# ATM90E36_Breakout.net
KiCad netlist of a schematic drawn in EAGLE
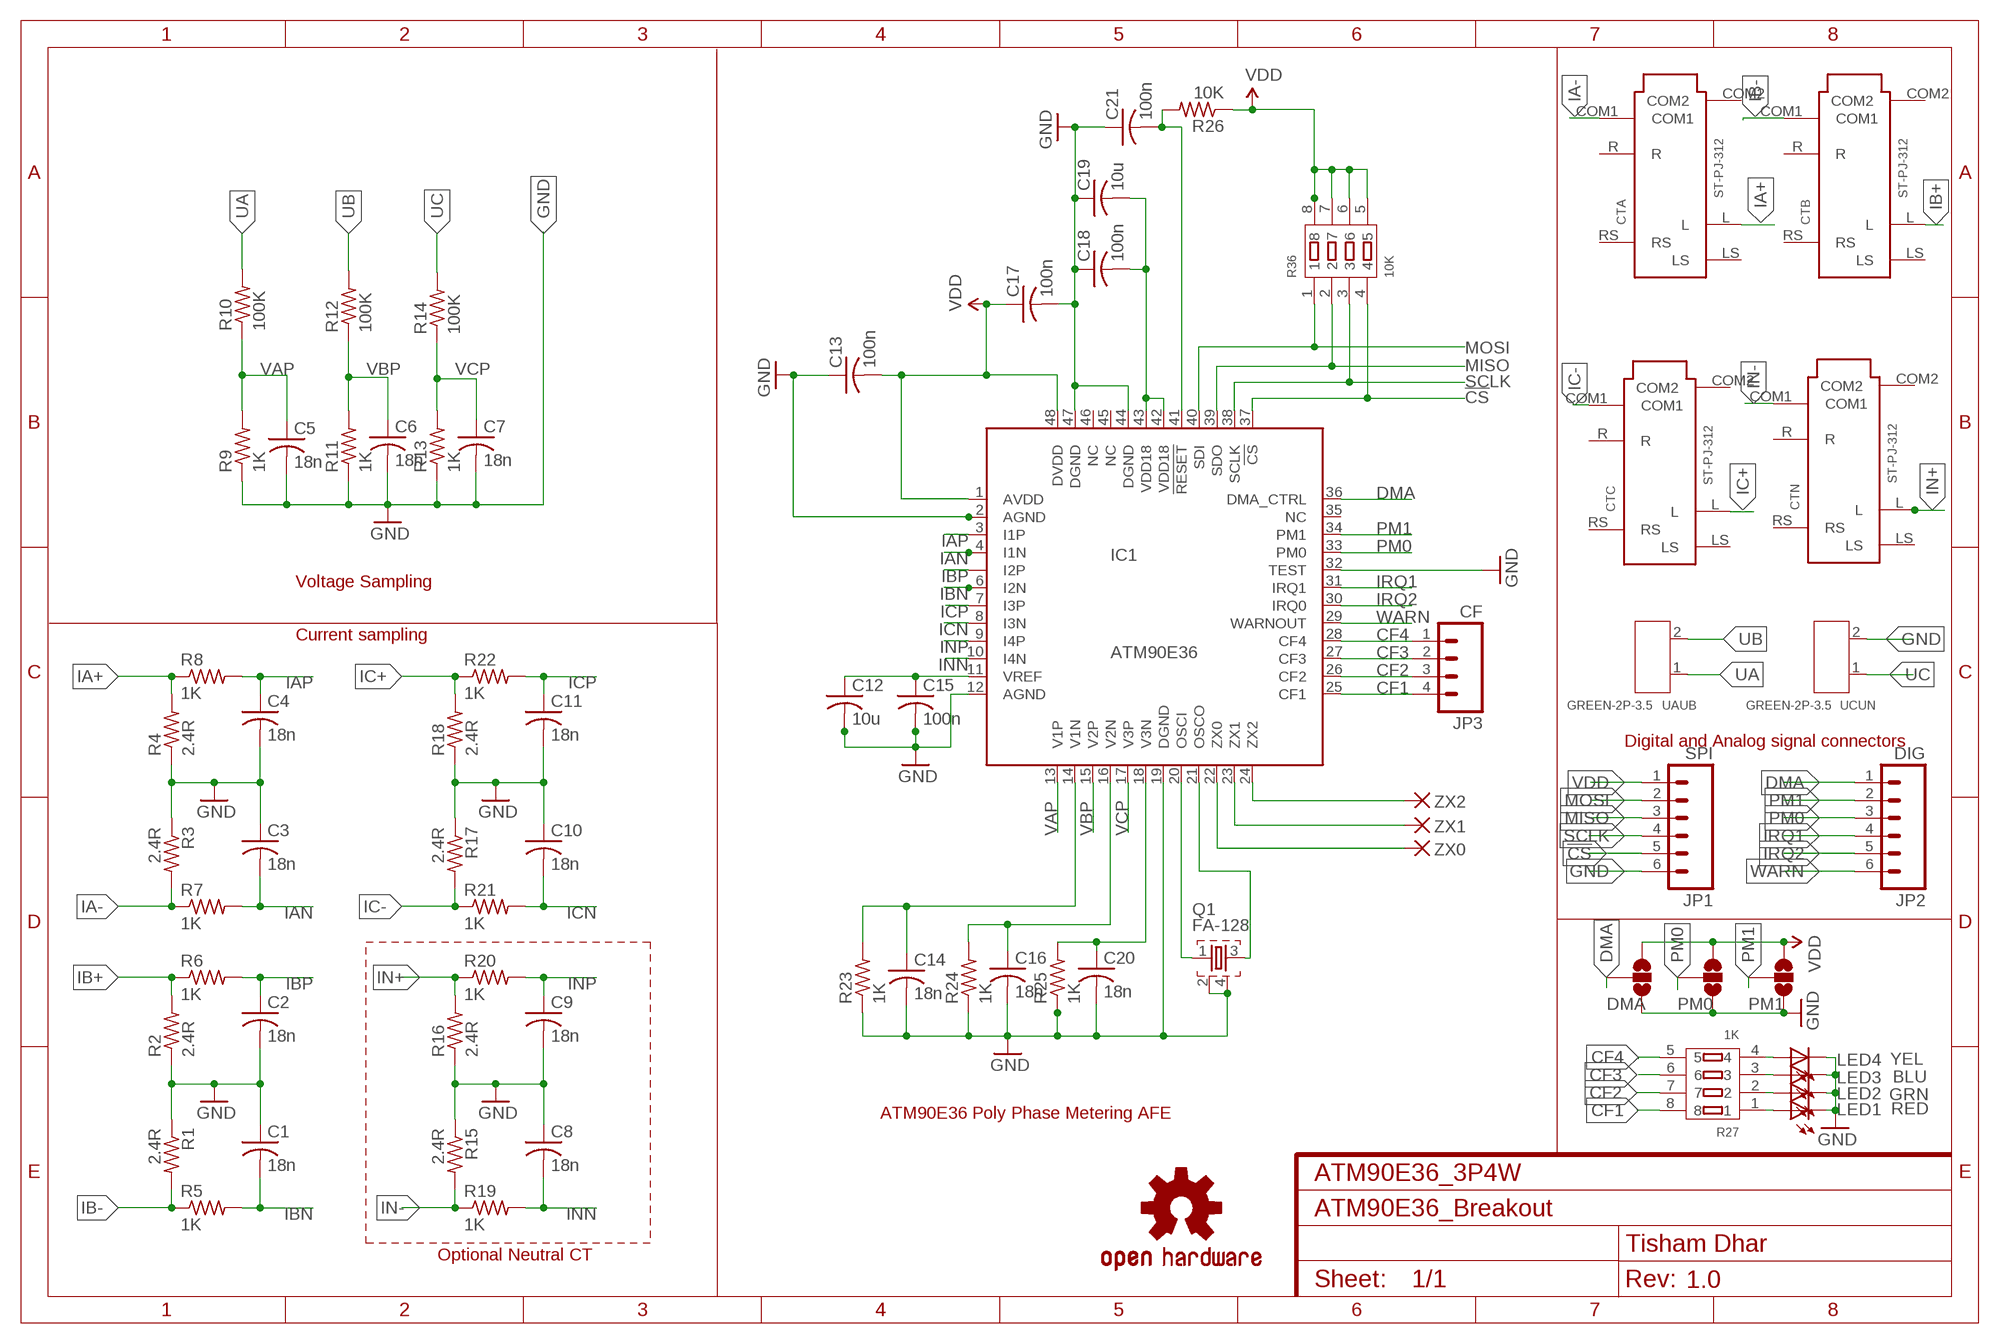
[diagram p0: schematic, sheet 1]

(export (version "E")
  (design (tool "Eeschema 10.0.6"))
  (components
    (comp (ref "C1")
      (value "18n")
      (footprint "eagle-import:C0603")
      (libsource (lib "eagle-import") (part "C-USC0603"))
    )
    (comp (ref "C2")
      (value "18n")
      (footprint "eagle-import:C0603")
      (libsource (lib "eagle-import") (part "C-USC0603"))
    )
    (comp (ref "C3")
      (value "18n")
      (footprint "eagle-import:C0603")
      (libsource (lib "eagle-import") (part "C-USC0603"))
    )
    (comp (ref "C4")
      (value "18n")
      (footprint "eagle-import:C0603")
      (libsource (lib "eagle-import") (part "C-USC0603"))
    )
    (comp (ref "C5")
      (value "18n")
      (footprint "eagle-import:C0603")
      (libsource (lib "eagle-import") (part "C-USC0603"))
    )
    (comp (ref "C6")
      (value "18n")
      (footprint "eagle-import:C0603")
      (libsource (lib "eagle-import") (part "C-USC0603"))
    )
    (comp (ref "C7")
      (value "18n")
      (footprint "eagle-import:C0603")
      (libsource (lib "eagle-import") (part "C-USC0603"))
    )
    (comp (ref "C8")
      (value "18n")
      (footprint "eagle-import:C0603")
      (libsource (lib "eagle-import") (part "C-USC0603"))
    )
    (comp (ref "C9")
      (value "18n")
      (footprint "eagle-import:C0603")
      (libsource (lib "eagle-import") (part "C-USC0603"))
    )
    (comp (ref "C10")
      (value "18n")
      (footprint "eagle-import:C0603")
      (libsource (lib "eagle-import") (part "C-USC0603"))
    )
    (comp (ref "C11")
      (value "18n")
      (footprint "eagle-import:C0603")
      (libsource (lib "eagle-import") (part "C-USC0603"))
    )
    (comp (ref "C12")
      (value "10u")
      (footprint "eagle-import:C0805")
      (libsource (lib "eagle-import") (part "C-USC0805"))
    )
    (comp (ref "C13")
      (value "100n")
      (footprint "eagle-import:C0603")
      (libsource (lib "eagle-import") (part "C-USC0603"))
    )
    (comp (ref "C14")
      (value "18n")
      (footprint "eagle-import:C0603")
      (libsource (lib "eagle-import") (part "C-USC0603"))
    )
    (comp (ref "C15")
      (value "100n")
      (footprint "eagle-import:C0603")
      (libsource (lib "eagle-import") (part "C-USC0603"))
    )
    (comp (ref "C16")
      (value "18n")
      (footprint "eagle-import:C0603")
      (libsource (lib "eagle-import") (part "C-USC0603"))
    )
    (comp (ref "C17")
      (value "100n")
      (footprint "eagle-import:C0603")
      (libsource (lib "eagle-import") (part "C-USC0603"))
    )
    (comp (ref "C18")
      (value "100n")
      (footprint "eagle-import:C0603")
      (libsource (lib "eagle-import") (part "C-USC0603"))
    )
    (comp (ref "C19")
      (value "10u")
      (footprint "eagle-import:C0805")
      (libsource (lib "eagle-import") (part "C-USC0805"))
    )
    (comp (ref "C20")
      (value "18n")
      (footprint "eagle-import:C0603")
      (libsource (lib "eagle-import") (part "C-USC0603"))
    )
    (comp (ref "C21")
      (value "100n")
      (footprint "eagle-import:C0603")
      (libsource (lib "eagle-import") (part "C-USC0603"))
    )
    (comp (ref "CTA")
      (value "ST-PJ-312")
      (footprint "eagle-import:AUDIO6P-SMD-3.5-14.0X6.4X5.0MM")
      (libsource (lib "eagle-import") (part "AUDIO-JACK-6P-SMD(ST-PJ-312)"))
    )
    (comp (ref "CTB")
      (value "ST-PJ-312")
      (footprint "eagle-import:AUDIO6P-SMD-3.5-14.0X6.4X5.0MM")
      (libsource (lib "eagle-import") (part "AUDIO-JACK-6P-SMD(ST-PJ-312)"))
    )
    (comp (ref "CTC")
      (value "ST-PJ-312")
      (footprint "eagle-import:AUDIO6P-SMD-3.5-14.0X6.4X5.0MM")
      (libsource (lib "eagle-import") (part "AUDIO-JACK-6P-SMD(ST-PJ-312)"))
    )
    (comp (ref "CTN")
      (value "ST-PJ-312")
      (footprint "eagle-import:AUDIO6P-SMD-3.5-14.0X6.4X5.0MM")
      (libsource (lib "eagle-import") (part "AUDIO-JACK-6P-SMD(ST-PJ-312)"))
    )
    (comp (ref "DMA")
      (value "JUMPER-PAD-3-NOFULL_BOX_SILK")
      (footprint "eagle-import:PAD-JUMPER-3-NO_YES_SILK_FULL_BOX")
      (libsource (lib "eagle-import") (part "JUMPER-PAD-3-NOFULL_BOX_SILK"))
    )
    (comp (ref "IC1")
      (value "ATM90E36")
      (footprint "eagle-import:TQFP48")
      (libsource (lib "eagle-import") (part "ATM90E36"))
    )
    (comp (ref "JP1")
      (value "SPI")
      (footprint "eagle-import:1X06_LOCK")
      (libsource (lib "eagle-import") (part "M06LOCK"))
    )
    (comp (ref "JP2")
      (value "DIG")
      (footprint "eagle-import:1X06_LOCK")
      (libsource (lib "eagle-import") (part "M06LOCK"))
    )
    (comp (ref "JP3")
      (value "CF")
      (footprint "eagle-import:1X04_LOCK")
      (libsource (lib "eagle-import") (part "M04LOCK"))
    )
    (comp (ref "LED1")
      (value "RED")
      (footprint "eagle-import:CHIP-LED0603")
      (libsource (lib "eagle-import") (part "LEDCHIP-LED0603"))
    )
    (comp (ref "LED2")
      (value "GRN")
      (footprint "eagle-import:CHIP-LED0603")
      (libsource (lib "eagle-import") (part "LEDCHIP-LED0603"))
    )
    (comp (ref "LED3")
      (value "BLU")
      (footprint "eagle-import:CHIP-LED0603")
      (libsource (lib "eagle-import") (part "LEDCHIP-LED0603"))
    )
    (comp (ref "LED4")
      (value "YEL")
      (footprint "eagle-import:CHIP-LED0603")
      (libsource (lib "eagle-import") (part "LEDCHIP-LED0603"))
    )
    (comp (ref "LOGO1")
      (value "OSHW-LOGOM")
      (footprint "eagle-import:OSHW-LOGO-M")
      (libsource (lib "eagle-import") (part "OSHW-LOGOM"))
    )
    (comp (ref "PM0")
      (value "JUMPER-PAD-3-NOFULL_BOX_SILK")
      (footprint "eagle-import:PAD-JUMPER-3-NO_YES_SILK_FULL_BOX")
      (libsource (lib "eagle-import") (part "JUMPER-PAD-3-NOFULL_BOX_SILK"))
    )
    (comp (ref "PM1")
      (value "JUMPER-PAD-3-NOFULL_BOX_SILK")
      (footprint "eagle-import:PAD-JUMPER-3-NO_YES_SILK_FULL_BOX")
      (libsource (lib "eagle-import") (part "JUMPER-PAD-3-NOFULL_BOX_SILK"))
    )
    (comp (ref "Q1")
      (value "FA-128")
      (footprint "eagle-import:FA-128")
      (libsource (lib "eagle-import") (part "FA-128"))
    )
    (comp (ref "R1")
      (value "2.4R")
      (footprint "eagle-import:R0603")
      (libsource (lib "eagle-import") (part "R-US_R0603"))
    )
    (comp (ref "R2")
      (value "2.4R")
      (footprint "eagle-import:R0603")
      (libsource (lib "eagle-import") (part "R-US_R0603"))
    )
    (comp (ref "R3")
      (value "2.4R")
      (footprint "eagle-import:R0603")
      (libsource (lib "eagle-import") (part "R-US_R0603"))
    )
    (comp (ref "R4")
      (value "2.4R")
      (footprint "eagle-import:R0603")
      (libsource (lib "eagle-import") (part "R-US_R0603"))
    )
    (comp (ref "R5")
      (value "1K")
      (footprint "eagle-import:R0603")
      (libsource (lib "eagle-import") (part "R-US_R0603"))
    )
    (comp (ref "R6")
      (value "1K")
      (footprint "eagle-import:R0603")
      (libsource (lib "eagle-import") (part "R-US_R0603"))
    )
    (comp (ref "R7")
      (value "1K")
      (footprint "eagle-import:R0603")
      (libsource (lib "eagle-import") (part "R-US_R0603"))
    )
    (comp (ref "R8")
      (value "1K")
      (footprint "eagle-import:R0603")
      (libsource (lib "eagle-import") (part "R-US_R0603"))
    )
    (comp (ref "R9")
      (value "1K")
      (footprint "eagle-import:R0603")
      (libsource (lib "eagle-import") (part "R-US_R0603"))
    )
    (comp (ref "R10")
      (value "100K")
      (footprint "eagle-import:R0603")
      (libsource (lib "eagle-import") (part "R-US_R0603"))
    )
    (comp (ref "R11")
      (value "1K")
      (footprint "eagle-import:R0603")
      (libsource (lib "eagle-import") (part "R-US_R0603"))
    )
    (comp (ref "R12")
      (value "100K")
      (footprint "eagle-import:R0603")
      (libsource (lib "eagle-import") (part "R-US_R0603"))
    )
    (comp (ref "R13")
      (value "1K")
      (footprint "eagle-import:R0603")
      (libsource (lib "eagle-import") (part "R-US_R0603"))
    )
    (comp (ref "R14")
      (value "100K")
      (footprint "eagle-import:R0603")
      (libsource (lib "eagle-import") (part "R-US_R0603"))
    )
    (comp (ref "R15")
      (value "2.4R")
      (footprint "eagle-import:R0603")
      (libsource (lib "eagle-import") (part "R-US_R0603"))
    )
    (comp (ref "R16")
      (value "2.4R")
      (footprint "eagle-import:R0603")
      (libsource (lib "eagle-import") (part "R-US_R0603"))
    )
    (comp (ref "R17")
      (value "2.4R")
      (footprint "eagle-import:R0603")
      (libsource (lib "eagle-import") (part "R-US_R0603"))
    )
    (comp (ref "R18")
      (value "2.4R")
      (footprint "eagle-import:R0603")
      (libsource (lib "eagle-import") (part "R-US_R0603"))
    )
    (comp (ref "R19")
      (value "1K")
      (footprint "eagle-import:R0603")
      (libsource (lib "eagle-import") (part "R-US_R0603"))
    )
    (comp (ref "R20")
      (value "1K")
      (footprint "eagle-import:R0603")
      (libsource (lib "eagle-import") (part "R-US_R0603"))
    )
    (comp (ref "R21")
      (value "1K")
      (footprint "eagle-import:R0603")
      (libsource (lib "eagle-import") (part "R-US_R0603"))
    )
    (comp (ref "R22")
      (value "1K")
      (footprint "eagle-import:R0603")
      (libsource (lib "eagle-import") (part "R-US_R0603"))
    )
    (comp (ref "R23")
      (value "1K")
      (footprint "eagle-import:R0603")
      (libsource (lib "eagle-import") (part "R-US_R0603"))
    )
    (comp (ref "R24")
      (value "1K")
      (footprint "eagle-import:R0603")
      (libsource (lib "eagle-import") (part "R-US_R0603"))
    )
    (comp (ref "R25")
      (value "1K")
      (footprint "eagle-import:R0603")
      (libsource (lib "eagle-import") (part "R-US_R0603"))
    )
    (comp (ref "R26")
      (value "10K")
      (footprint "eagle-import:R0603")
      (libsource (lib "eagle-import") (part "R-US_R0603"))
    )
    (comp (ref "R27")
      (value "1K")
      (footprint "eagle-import:RA1206-8")
      (fields (field (name "MPN") "Chip-Array-Series-1%"))
      (libsource (lib "eagle-import") (part "SMD-RES-ARRAY-1K-4R(RA1206-8)"))
    )
    (comp (ref "R36")
      (value "10K")
      (footprint "eagle-import:RA1206-8")
      (fields (field (name "MPN") "Chip-Array-Series-1%"))
      (libsource (lib "eagle-import") (part "SMD-RES-ARRAY-1K-4R(RA1206-8)"))
    )
    (comp (ref "UAUB")
      (value "GREEN-2P-3.5")
      (footprint "eagle-import:H2-3.5-7.0X7.0MM")
      (libsource (lib "eagle-import") (part "SCREW-TERMINAL-GREEN(2P-3.5)"))
    )
    (comp (ref "UCUN")
      (value "GREEN-2P-3.5")
      (footprint "eagle-import:H2-3.5-7.0X7.0MM")
      (libsource (lib "eagle-import") (part "SCREW-TERMINAL-GREEN(2P-3.5)"))
    )
    (comp (ref "ZX0")
      (value "ZX0")
      (footprint "eagle-import:SMD1,27-2,54")
      (libsource (lib "eagle-import") (part "SMD2"))
    )
    (comp (ref "ZX1")
      (value "ZX1")
      (footprint "eagle-import:SMD1,27-2,54")
      (libsource (lib "eagle-import") (part "SMD2"))
    )
    (comp (ref "ZX2")
      (value "ZX0")
      (footprint "eagle-import:SMD1,27-2,54")
      (libsource (lib "eagle-import") (part "SMD2"))
    )
  )
  (nets
    (net (code "1") (name "/IAN") (class "Default")
      (node (ref "C3") (pin "2") (pinfunction "2_2") (pintype "passive"))
      (node (ref "IC1") (pin "4") (pinfunction "I1N_4") (pintype "input"))
      (node (ref "R7") (pin "2") (pinfunction "2_2") (pintype "passive"))
    )
    (net (code "2") (name "/IAP") (class "Default")
      (node (ref "C4") (pin "1") (pinfunction "1_1") (pintype "passive"))
      (node (ref "IC1") (pin "3") (pinfunction "I1P_3") (pintype "input"))
      (node (ref "R8") (pin "2") (pinfunction "2_2") (pintype "passive"))
    )
    (net (code "3") (name "/IBN") (class "Default")
      (node (ref "C1") (pin "2") (pinfunction "2_2") (pintype "passive"))
      (node (ref "IC1") (pin "6") (pinfunction "I2N_6") (pintype "input"))
      (node (ref "R5") (pin "2") (pinfunction "2_2") (pintype "passive"))
    )
    (net (code "4") (name "/IBP") (class "Default")
      (node (ref "C2") (pin "1") (pinfunction "1_1") (pintype "passive"))
      (node (ref "IC1") (pin "5") (pinfunction "I2P_5") (pintype "input"))
      (node (ref "R6") (pin "2") (pinfunction "2_2") (pintype "passive"))
    )
    (net (code "5") (name "/ICN") (class "Default")
      (node (ref "C10") (pin "2") (pinfunction "2_2") (pintype "passive"))
      (node (ref "IC1") (pin "8") (pinfunction "I3N_8") (pintype "input"))
      (node (ref "R21") (pin "2") (pinfunction "2_2") (pintype "passive"))
    )
    (net (code "6") (name "/ICP") (class "Default")
      (node (ref "C11") (pin "1") (pinfunction "1_1") (pintype "passive"))
      (node (ref "IC1") (pin "7") (pinfunction "I3P_7") (pintype "input"))
      (node (ref "R22") (pin "2") (pinfunction "2_2") (pintype "passive"))
    )
    (net (code "7") (name "/INN") (class "Default")
      (node (ref "C8") (pin "2") (pinfunction "2_2") (pintype "passive"))
      (node (ref "IC1") (pin "10") (pinfunction "I4N_10") (pintype "input"))
      (node (ref "R19") (pin "2") (pinfunction "2_2") (pintype "passive"))
    )
    (net (code "8") (name "/INP") (class "Default")
      (node (ref "C9") (pin "1") (pinfunction "1_1") (pintype "passive"))
      (node (ref "IC1") (pin "9") (pinfunction "I4P_9") (pintype "input"))
      (node (ref "R20") (pin "2") (pinfunction "2_2") (pintype "passive"))
    )
    (net (code "9") (name "/VAP") (class "Default")
      (node (ref "C5") (pin "1") (pinfunction "1_1") (pintype "passive"))
      (node (ref "IC1") (pin "13") (pinfunction "V1P_13") (pintype "input"))
      (node (ref "R10") (pin "1") (pinfunction "1_1") (pintype "passive"))
      (node (ref "R9") (pin "2") (pinfunction "2_2") (pintype "passive"))
    )
    (net (code "10") (name "/VBP") (class "Default")
      (node (ref "C6") (pin "1") (pinfunction "1_1") (pintype "passive"))
      (node (ref "IC1") (pin "15") (pinfunction "V2P_15") (pintype "input"))
      (node (ref "R11") (pin "2") (pinfunction "2_2") (pintype "passive"))
      (node (ref "R12") (pin "1") (pinfunction "1_1") (pintype "passive"))
    )
    (net (code "11") (name "/VCP") (class "Default")
      (node (ref "C7") (pin "1") (pinfunction "1_1") (pintype "passive"))
      (node (ref "IC1") (pin "17") (pinfunction "V3P_17") (pintype "input"))
      (node (ref "R13") (pin "2") (pinfunction "2_2") (pintype "passive"))
      (node (ref "R14") (pin "1") (pinfunction "1_1") (pintype "passive"))
    )
    (net (code "12") (name "/~{CS}") (class "Default")
      (node (ref "IC1") (pin "37") (pinfunction "~{CS}_37") (pintype "input"))
      (node (ref "JP1") (pin "5") (pinfunction "5_5") (pintype "passive"))
      (node (ref "R36") (pin "4") (pinfunction "4_4") (pintype "bidirectional"))
    )
    (net (code "13") (name "CF1") (class "Default")
      (node (ref "IC1") (pin "25") (pinfunction "CF1_25") (pintype "output"))
      (node (ref "JP3") (pin "4") (pinfunction "4_4") (pintype "passive"))
      (node (ref "R27") (pin "8") (pinfunction "8_8") (pintype "bidirectional"))
    )
    (net (code "14") (name "CF2") (class "Default")
      (node (ref "IC1") (pin "26") (pinfunction "CF2_26") (pintype "output"))
      (node (ref "JP3") (pin "3") (pinfunction "3_3") (pintype "passive"))
      (node (ref "R27") (pin "7") (pinfunction "7_7") (pintype "bidirectional"))
    )
    (net (code "15") (name "CF3") (class "Default")
      (node (ref "IC1") (pin "27") (pinfunction "CF3_27") (pintype "output"))
      (node (ref "JP3") (pin "2") (pinfunction "2_2") (pintype "passive"))
      (node (ref "R27") (pin "6") (pinfunction "6_6") (pintype "bidirectional"))
    )
    (net (code "16") (name "CF4") (class "Default")
      (node (ref "IC1") (pin "28") (pinfunction "CF4_28") (pintype "output"))
      (node (ref "JP3") (pin "1") (pinfunction "1_1") (pintype "passive"))
      (node (ref "R27") (pin "5") (pinfunction "5_5") (pintype "bidirectional"))
    )
    (net (code "17") (name "DMA") (class "Default")
      (node (ref "DMA") (pin "2") (pinfunction "2_2") (pintype "passive"))
      (node (ref "IC1") (pin "36") (pinfunction "DMA_CTRL_36") (pintype "input"))
      (node (ref "JP2") (pin "1") (pinfunction "1_1") (pintype "passive"))
    )
    (net (code "18") (name "GND") (class "Default")
      (node (ref "C1") (pin "1") (pinfunction "1_1") (pintype "passive"))
      (node (ref "C10") (pin "1") (pinfunction "1_1") (pintype "passive"))
      (node (ref "C11") (pin "2") (pinfunction "2_2") (pintype "passive"))
      (node (ref "C12") (pin "2") (pinfunction "2_2") (pintype "passive"))
      (node (ref "C13") (pin "1") (pinfunction "1_1") (pintype "passive"))
      (node (ref "C14") (pin "2") (pinfunction "2_2") (pintype "passive"))
      (node (ref "C15") (pin "2") (pinfunction "2_2") (pintype "passive"))
      (node (ref "C16") (pin "2") (pinfunction "2_2") (pintype "passive"))
      (node (ref "C17") (pin "2") (pinfunction "2_2") (pintype "passive"))
      (node (ref "C18") (pin "1") (pinfunction "1_1") (pintype "passive"))
      (node (ref "C19") (pin "1") (pinfunction "1_1") (pintype "passive"))
      (node (ref "C2") (pin "2") (pinfunction "2_2") (pintype "passive"))
      (node (ref "C20") (pin "2") (pinfunction "2_2") (pintype "passive"))
      (node (ref "C21") (pin "1") (pinfunction "1_1") (pintype "passive"))
      (node (ref "C3") (pin "1") (pinfunction "1_1") (pintype "passive"))
      (node (ref "C4") (pin "2") (pinfunction "2_2") (pintype "passive"))
      (node (ref "C5") (pin "2") (pinfunction "2_2") (pintype "passive"))
      (node (ref "C6") (pin "2") (pinfunction "2_2") (pintype "passive"))
      (node (ref "C7") (pin "2") (pinfunction "2_2") (pintype "passive"))
      (node (ref "C8") (pin "1") (pinfunction "1_1") (pintype "passive"))
      (node (ref "C9") (pin "2") (pinfunction "2_2") (pintype "passive"))
      (node (ref "DMA") (pin "3") (pinfunction "3_3") (pintype "passive"))
      (node (ref "IC1") (pin "12") (pinfunction "AGND_12") (pintype "power_in"))
      (node (ref "IC1") (pin "19") (pinfunction "DGND_19") (pintype "power_in"))
      (node (ref "IC1") (pin "2") (pinfunction "AGND_2") (pintype "power_in"))
      (node (ref "IC1") (pin "32") (pinfunction "TEST_32") (pintype "power_in"))
      (node (ref "IC1") (pin "44") (pinfunction "DGND_44") (pintype "power_in"))
      (node (ref "IC1") (pin "47") (pinfunction "DGND_47") (pintype "power_in"))
      (node (ref "JP1") (pin "6") (pinfunction "6_6") (pintype "passive"))
      (node (ref "LED1") (pin "C") (pinfunction "C_C") (pintype "passive"))
      (node (ref "LED2") (pin "C") (pinfunction "C_C") (pintype "passive"))
      (node (ref "LED3") (pin "C") (pinfunction "C_C") (pintype "passive"))
      (node (ref "LED4") (pin "C") (pinfunction "C_C") (pintype "passive"))
      (node (ref "PM0") (pin "3") (pinfunction "3_3") (pintype "passive"))
      (node (ref "PM1") (pin "3") (pinfunction "3_3") (pintype "passive"))
      (node (ref "Q1") (pin "2") (pinfunction "2_2") (pintype "passive"))
      (node (ref "Q1") (pin "4") (pinfunction "4_4") (pintype "passive"))
      (node (ref "R1") (pin "1") (pinfunction "1_1") (pintype "passive"))
      (node (ref "R11") (pin "1") (pinfunction "1_1") (pintype "passive"))
      (node (ref "R13") (pin "1") (pinfunction "1_1") (pintype "passive"))
      (node (ref "R15") (pin "1") (pinfunction "1_1") (pintype "passive"))
      (node (ref "R16") (pin "1") (pinfunction "1_1") (pintype "passive"))
      (node (ref "R17") (pin "1") (pinfunction "1_1") (pintype "passive"))
      (node (ref "R18") (pin "1") (pinfunction "1_1") (pintype "passive"))
      (node (ref "R2") (pin "1") (pinfunction "1_1") (pintype "passive"))
      (node (ref "R23") (pin "1") (pinfunction "1_1") (pintype "passive"))
      (node (ref "R24") (pin "1") (pinfunction "1_1") (pintype "passive"))
      (node (ref "R25") (pin "1") (pinfunction "1_1") (pintype "passive"))
      (node (ref "R3") (pin "1") (pinfunction "1_1") (pintype "passive"))
      (node (ref "R4") (pin "1") (pinfunction "1_1") (pintype "passive"))
      (node (ref "R9") (pin "1") (pinfunction "1_1") (pintype "passive"))
      (node (ref "UCUN") (pin "2") (pinfunction "2_2") (pintype "bidirectional"))
    )
    (net (code "19") (name "IA+") (class "Default")
      (node (ref "CTA") (pin "L") (pinfunction "L_L") (pintype "bidirectional"))
      (node (ref "R4") (pin "2") (pinfunction "2_2") (pintype "passive"))
      (node (ref "R8") (pin "1") (pinfunction "1_1") (pintype "passive"))
    )
    (net (code "20") (name "IA-") (class "Default")
      (node (ref "CTA") (pin "COM1") (pinfunction "COM1_COM1") (pintype "bidirectional"))
      (node (ref "R3") (pin "2") (pinfunction "2_2") (pintype "passive"))
      (node (ref "R7") (pin "1") (pinfunction "1_1") (pintype "passive"))
    )
    (net (code "21") (name "IB+") (class "Default")
      (node (ref "CTB") (pin "L") (pinfunction "L_L") (pintype "bidirectional"))
      (node (ref "R2") (pin "2") (pinfunction "2_2") (pintype "passive"))
      (node (ref "R6") (pin "1") (pinfunction "1_1") (pintype "passive"))
    )
    (net (code "22") (name "IB-") (class "Default")
      (node (ref "CTB") (pin "COM1") (pinfunction "COM1_COM1") (pintype "bidirectional"))
      (node (ref "R1") (pin "2") (pinfunction "2_2") (pintype "passive"))
      (node (ref "R5") (pin "1") (pinfunction "1_1") (pintype "passive"))
    )
    (net (code "23") (name "IC+") (class "Default")
      (node (ref "CTC") (pin "L") (pinfunction "L_L") (pintype "bidirectional"))
      (node (ref "R18") (pin "2") (pinfunction "2_2") (pintype "passive"))
      (node (ref "R22") (pin "1") (pinfunction "1_1") (pintype "passive"))
    )
    (net (code "24") (name "IC-") (class "Default")
      (node (ref "CTC") (pin "COM1") (pinfunction "COM1_COM1") (pintype "bidirectional"))
      (node (ref "R17") (pin "2") (pinfunction "2_2") (pintype "passive"))
      (node (ref "R21") (pin "1") (pinfunction "1_1") (pintype "passive"))
    )
    (net (code "25") (name "IN+") (class "Default")
      (node (ref "CTN") (pin "L") (pinfunction "L_L") (pintype "bidirectional"))
      (node (ref "R16") (pin "2") (pinfunction "2_2") (pintype "passive"))
      (node (ref "R20") (pin "1") (pinfunction "1_1") (pintype "passive"))
    )
    (net (code "26") (name "IN-") (class "Default")
      (node (ref "CTN") (pin "COM1") (pinfunction "COM1_COM1") (pintype "bidirectional"))
      (node (ref "R15") (pin "2") (pinfunction "2_2") (pintype "passive"))
      (node (ref "R19") (pin "1") (pinfunction "1_1") (pintype "passive"))
    )
    (net (code "27") (name "IRQ1") (class "Default")
      (node (ref "IC1") (pin "31") (pinfunction "IRQ1_31") (pintype "output"))
      (node (ref "JP2") (pin "4") (pinfunction "4_4") (pintype "passive"))
    )
    (net (code "28") (name "IRQ2") (class "Default")
      (node (ref "IC1") (pin "30") (pinfunction "IRQ0_30") (pintype "output"))
      (node (ref "JP2") (pin "5") (pinfunction "5_5") (pintype "passive"))
    )
    (net (code "29") (name "MISO") (class "Default")
      (node (ref "IC1") (pin "39") (pinfunction "SDO_39") (pintype "output"))
      (node (ref "JP1") (pin "3") (pinfunction "3_3") (pintype "passive"))
      (node (ref "R36") (pin "2") (pinfunction "2_2") (pintype "bidirectional"))
    )
    (net (code "30") (name "MOSI") (class "Default")
      (node (ref "IC1") (pin "40") (pinfunction "SDI_40") (pintype "input"))
      (node (ref "JP1") (pin "2") (pinfunction "2_2") (pintype "passive"))
      (node (ref "R36") (pin "1") (pinfunction "1_1") (pintype "bidirectional"))
    )
    (net (code "31") (name "Net-(C18-Pad2)") (class "Default")
      (node (ref "C18") (pin "2") (pinfunction "2_2") (pintype "passive"))
      (node (ref "C19") (pin "2") (pinfunction "2_2") (pintype "passive"))
      (node (ref "IC1") (pin "42") (pinfunction "VDD18_42") (pintype "power_in"))
      (node (ref "IC1") (pin "43") (pinfunction "VDD18_43") (pintype "power_in"))
    )
    (net (code "32") (name "Net-(IC1-OSCI)") (class "Default")
      (node (ref "IC1") (pin "20") (pinfunction "OSCI_20") (pintype "input"))
      (node (ref "Q1") (pin "1") (pinfunction "1_1") (pintype "passive"))
    )
    (net (code "33") (name "Net-(IC1-OSCO)") (class "Default")
      (node (ref "IC1") (pin "21") (pinfunction "OSCO_21") (pintype "output"))
      (node (ref "Q1") (pin "3") (pinfunction "3_3") (pintype "passive"))
    )
    (net (code "34") (name "Net-(IC1-V1N)") (class "Default")
      (node (ref "C14") (pin "1") (pinfunction "1_1") (pintype "passive"))
      (node (ref "IC1") (pin "14") (pinfunction "V1N_14") (pintype "input"))
      (node (ref "R23") (pin "2") (pinfunction "2_2") (pintype "passive"))
    )
    (net (code "35") (name "Net-(IC1-V2N)") (class "Default")
      (node (ref "C16") (pin "1") (pinfunction "1_1") (pintype "passive"))
      (node (ref "IC1") (pin "16") (pinfunction "V2N_16") (pintype "input"))
      (node (ref "R24") (pin "2") (pinfunction "2_2") (pintype "passive"))
    )
    (net (code "36") (name "Net-(IC1-V3N)") (class "Default")
      (node (ref "C20") (pin "1") (pinfunction "1_1") (pintype "passive"))
      (node (ref "IC1") (pin "18") (pinfunction "V3N_18") (pintype "input"))
      (node (ref "R25") (pin "2") (pinfunction "2_2") (pintype "passive"))
    )
    (net (code "37") (name "Net-(IC1-VREF)") (class "Default")
      (node (ref "C12") (pin "1") (pinfunction "1_1") (pintype "passive"))
      (node (ref "C15") (pin "1") (pinfunction "1_1") (pintype "passive"))
      (node (ref "IC1") (pin "11") (pinfunction "VREF_11") (pintype "bidirectional"))
    )
    (net (code "38") (name "Net-(IC1-ZX0)") (class "Default")
      (node (ref "IC1") (pin "22") (pinfunction "ZX0_22") (pintype "output"))
      (node (ref "ZX0") (pin "1") (pinfunction "P_1") (pintype "passive"))
    )
    (net (code "39") (name "Net-(IC1-ZX1)") (class "Default")
      (node (ref "IC1") (pin "23") (pinfunction "ZX1_23") (pintype "output"))
      (node (ref "ZX1") (pin "1") (pinfunction "P_1") (pintype "passive"))
    )
    (net (code "40") (name "Net-(IC1-ZX2)") (class "Default")
      (node (ref "IC1") (pin "24") (pinfunction "ZX2_24") (pintype "output"))
      (node (ref "ZX2") (pin "1") (pinfunction "P_1") (pintype "passive"))
    )
    (net (code "41") (name "Net-(IC1-~{RESET})") (class "Default")
      (node (ref "C21") (pin "2") (pinfunction "2_2") (pintype "passive"))
      (node (ref "IC1") (pin "41") (pinfunction "~{RESET}_41") (pintype "input"))
      (node (ref "R26") (pin "2") (pinfunction "2_2") (pintype "passive"))
    )
    (net (code "42") (name "Net-(LED1-PadA)") (class "Default")
      (node (ref "LED1") (pin "A") (pinfunction "A_A") (pintype "passive"))
      (node (ref "R27") (pin "1") (pinfunction "1_1") (pintype "bidirectional"))
    )
    (net (code "43") (name "Net-(LED2-PadA)") (class "Default")
      (node (ref "LED2") (pin "A") (pinfunction "A_A") (pintype "passive"))
      (node (ref "R27") (pin "2") (pinfunction "2_2") (pintype "bidirectional"))
    )
    (net (code "44") (name "Net-(LED3-PadA)") (class "Default")
      (node (ref "LED3") (pin "A") (pinfunction "A_A") (pintype "passive"))
      (node (ref "R27") (pin "3") (pinfunction "3_3") (pintype "bidirectional"))
    )
    (net (code "45") (name "Net-(LED4-PadA)") (class "Default")
      (node (ref "LED4") (pin "A") (pinfunction "A_A") (pintype "passive"))
      (node (ref "R27") (pin "4") (pinfunction "4_4") (pintype "bidirectional"))
    )
    (net (code "46") (name "PM0") (class "Default")
      (node (ref "IC1") (pin "33") (pinfunction "PM0_33") (pintype "input"))
      (node (ref "JP2") (pin "3") (pinfunction "3_3") (pintype "passive"))
      (node (ref "PM0") (pin "2") (pinfunction "2_2") (pintype "passive"))
    )
    (net (code "47") (name "PM1") (class "Default")
      (node (ref "IC1") (pin "34") (pinfunction "PM1_34") (pintype "input"))
      (node (ref "JP2") (pin "2") (pinfunction "2_2") (pintype "passive"))
      (node (ref "PM1") (pin "2") (pinfunction "2_2") (pintype "passive"))
    )
    (net (code "48") (name "SCLK") (class "Default")
      (node (ref "IC1") (pin "38") (pinfunction "SCLK_38") (pintype "input"))
      (node (ref "JP1") (pin "4") (pinfunction "4_4") (pintype "passive"))
      (node (ref "R36") (pin "3") (pinfunction "3_3") (pintype "bidirectional"))
    )
    (net (code "49") (name "UA") (class "Default")
      (node (ref "R10") (pin "2") (pinfunction "2_2") (pintype "passive"))
      (node (ref "UAUB") (pin "1") (pinfunction "1_1") (pintype "bidirectional"))
    )
    (net (code "50") (name "UB") (class "Default")
      (node (ref "R12") (pin "2") (pinfunction "2_2") (pintype "passive"))
      (node (ref "UAUB") (pin "2") (pinfunction "2_2") (pintype "bidirectional"))
    )
    (net (code "51") (name "UC") (class "Default")
      (node (ref "R14") (pin "2") (pinfunction "2_2") (pintype "passive"))
      (node (ref "UCUN") (pin "1") (pinfunction "1_1") (pintype "bidirectional"))
    )
    (net (code "52") (name "VDD") (class "Default")
      (node (ref "C13") (pin "2") (pinfunction "2_2") (pintype "passive"))
      (node (ref "C17") (pin "1") (pinfunction "1_1") (pintype "passive"))
      (node (ref "DMA") (pin "1") (pinfunction "1_1") (pintype "passive"))
      (node (ref "IC1") (pin "1") (pinfunction "AVDD_1") (pintype "power_in"))
      (node (ref "IC1") (pin "48") (pinfunction "DVDD_48") (pintype "power_in"))
      (node (ref "JP1") (pin "1") (pinfunction "1_1") (pintype "passive"))
      (node (ref "PM0") (pin "1") (pinfunction "1_1") (pintype "passive"))
      (node (ref "PM1") (pin "1") (pinfunction "1_1") (pintype "passive"))
      (node (ref "R26") (pin "1") (pinfunction "1_1") (pintype "passive"))
      (node (ref "R36") (pin "5") (pinfunction "5_5") (pintype "bidirectional"))
      (node (ref "R36") (pin "6") (pinfunction "6_6") (pintype "bidirectional"))
      (node (ref "R36") (pin "7") (pinfunction "7_7") (pintype "bidirectional"))
      (node (ref "R36") (pin "8") (pinfunction "8_8") (pintype "bidirectional"))
    )
    (net (code "53") (name "WARN") (class "Default")
      (node (ref "IC1") (pin "29") (pinfunction "WARNOUT_29") (pintype "output"))
      (node (ref "JP2") (pin "6") (pinfunction "6_6") (pintype "passive"))
    )
    (net (code "54") (name "unconnected-(CTA-PadCOM2)") (class "Default")
      (node (ref "CTA") (pin "COM2") (pinfunction "COM2_COM2") (pintype "bidirectional"))
    )
    (net (code "55") (name "unconnected-(CTA-PadLS)") (class "Default")
      (node (ref "CTA") (pin "LS") (pinfunction "LS_LS") (pintype "bidirectional"))
    )
    (net (code "56") (name "unconnected-(CTA-PadR)") (class "Default")
      (node (ref "CTA") (pin "R") (pinfunction "R_R") (pintype "bidirectional"))
    )
    (net (code "57") (name "unconnected-(CTA-PadRS)") (class "Default")
      (node (ref "CTA") (pin "RS") (pinfunction "RS_RS") (pintype "bidirectional"))
    )
    (net (code "58") (name "unconnected-(CTB-PadCOM2)") (class "Default")
      (node (ref "CTB") (pin "COM2") (pinfunction "COM2_COM2") (pintype "bidirectional"))
    )
    (net (code "59") (name "unconnected-(CTB-PadLS)") (class "Default")
      (node (ref "CTB") (pin "LS") (pinfunction "LS_LS") (pintype "bidirectional"))
    )
    (net (code "60") (name "unconnected-(CTB-PadR)") (class "Default")
      (node (ref "CTB") (pin "R") (pinfunction "R_R") (pintype "bidirectional"))
    )
    (net (code "61") (name "unconnected-(CTB-PadRS)") (class "Default")
      (node (ref "CTB") (pin "RS") (pinfunction "RS_RS") (pintype "bidirectional"))
    )
    (net (code "62") (name "unconnected-(CTC-PadCOM2)") (class "Default")
      (node (ref "CTC") (pin "COM2") (pinfunction "COM2_COM2") (pintype "bidirectional"))
    )
    (net (code "63") (name "unconnected-(CTC-PadLS)") (class "Default")
      (node (ref "CTC") (pin "LS") (pinfunction "LS_LS") (pintype "bidirectional"))
    )
    (net (code "64") (name "unconnected-(CTC-PadR)") (class "Default")
      (node (ref "CTC") (pin "R") (pinfunction "R_R") (pintype "bidirectional"))
    )
    (net (code "65") (name "unconnected-(CTC-PadRS)") (class "Default")
      (node (ref "CTC") (pin "RS") (pinfunction "RS_RS") (pintype "bidirectional"))
    )
    (net (code "66") (name "unconnected-(CTN-PadCOM2)") (class "Default")
      (node (ref "CTN") (pin "COM2") (pinfunction "COM2_COM2") (pintype "bidirectional"))
    )
    (net (code "67") (name "unconnected-(CTN-PadLS)") (class "Default")
      (node (ref "CTN") (pin "LS") (pinfunction "LS_LS") (pintype "bidirectional"))
    )
    (net (code "68") (name "unconnected-(CTN-PadR)") (class "Default")
      (node (ref "CTN") (pin "R") (pinfunction "R_R") (pintype "bidirectional"))
    )
    (net (code "69") (name "unconnected-(CTN-PadRS)") (class "Default")
      (node (ref "CTN") (pin "RS") (pinfunction "RS_RS") (pintype "bidirectional"))
    )
    (net (code "70") (name "unconnected-(IC1-NC-Pad35)") (class "Default")
      (node (ref "IC1") (pin "35") (pinfunction "NC_35") (pintype "no_connect"))
    )
    (net (code "71") (name "unconnected-(IC1-NC-Pad45)") (class "Default")
      (node (ref "IC1") (pin "45") (pinfunction "NC_45") (pintype "no_connect"))
    )
    (net (code "72") (name "unconnected-(IC1-NC-Pad46)") (class "Default")
      (node (ref "IC1") (pin "46") (pinfunction "NC_46") (pintype "no_connect"))
    )
  )
)
